# THS3201.net
KiCad netlist of a schematic drawn in Altium Designer
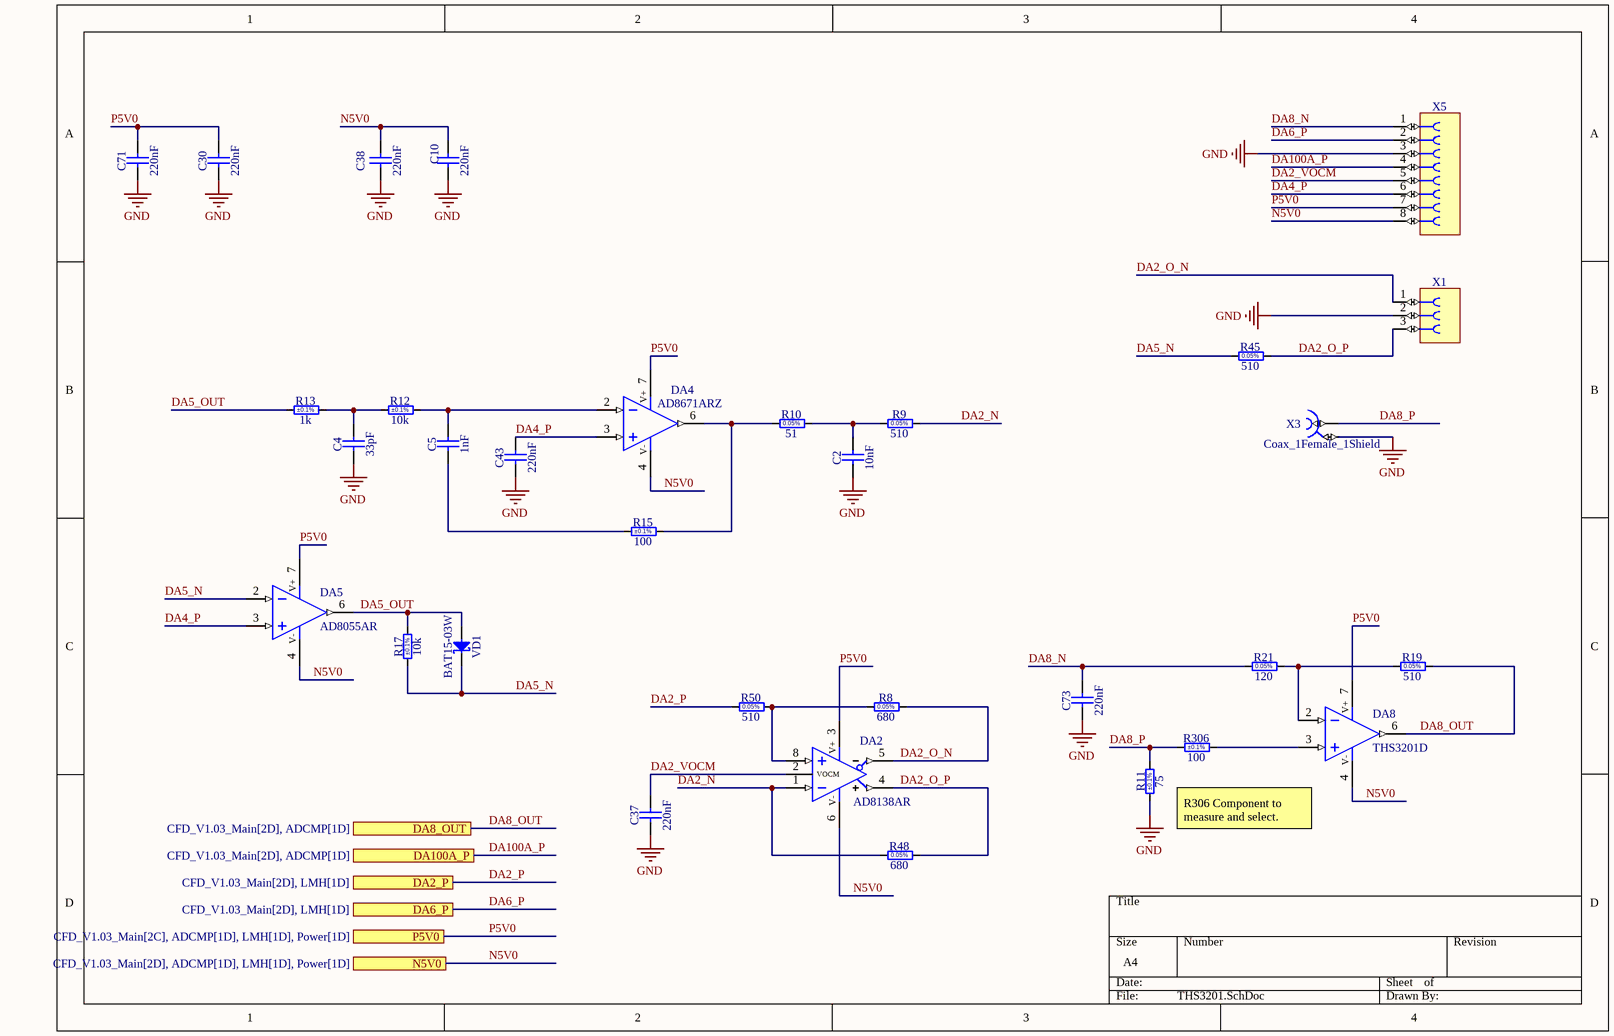
[diagram p0: THS3201.SchDoc]

(export (version "E")
  (design (tool "Eeschema 10.0.6"))
  (components
    (comp (ref "C2")
      (value "10nF")
      (footprint "CAPC2012X135N")
      (description "Non-polarised capacitor")
      (fields
        (field (name "PART NUMBER") "CC0805_10NF_50V_2%_C0G")
        (field (name "VOLTAGE") "50V")
        (field (name "AUTHOR") "CERN DEM HF")
      )
      (libsource (lib "Capacitors") (part "Capacitor - non polarized"))
    )
    (comp (ref "C4")
      (value "33pF")
      (footprint "CAPC2013X115N")
      (description "Non-polarised capacitor")
      (fields
        (field (name "PART NUMBER") "CC0805_33PF_200V_1%_NP0")
        (field (name "VOLTAGE") "200V")
        (field (name "AUTHOR") "CERN DEM HF")
      )
      (libsource (lib "Capacitors") (part "Capacitor - non polarized"))
    )
    (comp (ref "C5")
      (value "1nF")
      (footprint "CAPC2013X100N")
      (description "Non-polarised capacitor")
      (fields
        (field (name "PART NUMBER") "CC0805_1NF_25V_1%_C0G")
        (field (name "VOLTAGE") "25V")
        (field (name "AUTHOR") "CERN DEM JLC")
      )
      (libsource (lib "Capacitors") (part "Capacitor - non polarized"))
    )
    (comp (ref "C10")
      (value "220nF")
      (footprint "CAPC2012X135N")
      (description "Non-polarised capacitor")
      (fields
        (field (name "PART NUMBER") "CC0805_220NF_50V_10%_X7R")
        (field (name "VOLTAGE") "50V")
        (field (name "AUTHOR") "CERN DEM JLC")
      )
      (libsource (lib "Capacitors") (part "Capacitor - non polarized"))
    )
    (comp (ref "C30")
      (value "220nF")
      (footprint "CAPC2012X135N")
      (description "Non-polarised capacitor")
      (fields
        (field (name "PART NUMBER") "CC0805_220NF_50V_10%_X7R")
        (field (name "VOLTAGE") "50V")
        (field (name "AUTHOR") "CERN DEM JLC")
      )
      (libsource (lib "Capacitors") (part "Capacitor - non polarized"))
    )
    (comp (ref "C37")
      (value "220nF")
      (footprint "CAPC2012X135N")
      (description "Non-polarised capacitor")
      (fields
        (field (name "PART NUMBER") "CC0805_220NF_50V_10%_X7R")
        (field (name "VOLTAGE") "50V")
        (field (name "AUTHOR") "CERN DEM JLC")
      )
      (libsource (lib "Capacitors") (part "Capacitor - non polarized"))
    )
    (comp (ref "C38")
      (value "220nF")
      (footprint "CAPC2012X135N")
      (description "Non-polarised capacitor")
      (fields
        (field (name "PART NUMBER") "CC0805_220NF_50V_10%_X7R")
        (field (name "VOLTAGE") "50V")
        (field (name "AUTHOR") "CERN DEM JLC")
      )
      (libsource (lib "Capacitors") (part "Capacitor - non polarized"))
    )
    (comp (ref "C43")
      (value "220nF")
      (footprint "CAPC2012X135N")
      (description "Non-polarised capacitor")
      (fields
        (field (name "PART NUMBER") "CC0805_220NF_50V_10%_X7R")
        (field (name "VOLTAGE") "50V")
        (field (name "AUTHOR") "CERN DEM JLC")
      )
      (libsource (lib "Capacitors") (part "Capacitor - non polarized"))
    )
    (comp (ref "C71")
      (value "220nF")
      (footprint "CAPC2012X135N")
      (description "Non-polarised capacitor")
      (fields
        (field (name "PART NUMBER") "CC0805_220NF_50V_10%_X7R")
        (field (name "VOLTAGE") "50V")
        (field (name "AUTHOR") "CERN DEM JLC")
      )
      (libsource (lib "Capacitors") (part "Capacitor - non polarized"))
    )
    (comp (ref "C73")
      (value "220nF")
      (footprint "CAPC2012X135N")
      (description "Non-polarised capacitor")
      (fields
        (field (name "PART NUMBER") "CC0805_220NF_50V_10%_X7R")
        (field (name "VOLTAGE") "50V")
        (field (name "AUTHOR") "CERN DEM JLC")
      )
      (libsource (lib "Capacitors") (part "Capacitor - non polarized"))
    )
    (comp (ref "DA2")
      (value "AD8138AR")
      (footprint "SOIC127P600X175-8N")
      (description "Differential Amplifier")
      (fields (field (name "MANUFACTURER") "ANALOG DEVICES") (field (name "AUTHOR") "CERN DEM JLC"))
      (libsource (lib "ICs And Semiconductors") (part "Differential Amplifier Type1"))
    )
    (comp (ref "DA4")
      (value "AD8671ARZ")
      (footprint "SOIC127P600X175-8N")
      (description "Operational Amplifier")
      (fields
        (field (name "MANUFACTURER") "ANALOG DEVICES")
        (field (name "MANUFACTURER PART NUMBER") "AD8671AR")
        (field (name "AUTHOR") "CERN DEM JLC")
      )
      (libsource (lib "ICs And Semiconductors") (part "Operational Amplifier Type1"))
    )
    (comp (ref "DA5")
      (value "AD8055AR")
      (footprint "SOIC127P600X175-8N")
      (description "Operational Amplifier")
      (fields (field (name "MANUFACTURER") "ANALOG DEVICES") (field (name "AUTHOR") "CERN DEM HF"))
      (libsource (lib "ICs And Semiconductors") (part "Operational Amplifier Type1"))
    )
    (comp (ref "DA8")
      (value "THS3201D")
      (footprint "SOIC127P600X175-8N")
      (description "Operational Amplifier")
      (fields (field (name "MANUFACTURER") "TEXAS INSTRUMENTS") (field (name "AUTHOR") "CERN DEM HF"))
      (libsource (lib "ICs And Semiconductors") (part "Operational Amplifier Type1"))
    )
    (comp (ref "R8")
      (value "680")
      (footprint "RESC2012X60N")
      (description "Resistor - 0.05%")
      (fields
        (field (name "PART NUMBER") "R0805_680R_0.05%_0.125W_10PPM")
        (field (name "POWER") "0.1W")
        (field (name "AUTHOR") "CERN DEM HF")
      )
      (libsource (lib "Resistors") (part "Resistor - 0.05%"))
    )
    (comp (ref "R9")
      (value "510")
      (footprint "RESC1608X55N")
      (description "Resistor - 0.05%")
      (fields
        (field (name "PART NUMBER") "R0603_510R_0.1%_0.1W_10PPM")
        (field (name "POWER") "0.1W")
        (field (name "AUTHOR") "CERN DEM HF")
      )
      (libsource (lib "Resistors") (part "Resistor - 0.05%"))
    )
    (comp (ref "R10")
      (value "51")
      (footprint "RESC2012X60N")
      (description "Resistor - 0.05%")
      (fields
        (field (name "PART NUMBER") "R0805_51R_0.05%_0.125W_10PPM")
        (field (name "POWER") "0.1W")
        (field (name "AUTHOR") "CERN DEM HF")
      )
      (libsource (lib "Resistors") (part "Resistor - 0.05%"))
    )
    (comp (ref "R11")
      (value "75")
      (footprint "RESC1608X55N")
      (description "Resistor - 0.1%")
      (fields
        (field (name "TOLERANCE") "±0.1%")
        (field (name "PART NUMBER") "R0603_75R_0.1%_0.063W_10PPM")
        (field (name "POWER") "0.063W")
        (field (name "AUTHOR") "CERN DEM JLC")
      )
      (libsource (lib "Resistors") (part "Resistor - 0.1%"))
    )
    (comp (ref "R12")
      (value "10k")
      (footprint "RESC2012X60N")
      (description "Resistor - 0.1%")
      (fields
        (field (name "TOLERANCE") "±0.1%")
        (field (name "PART NUMBER") "R0805_10K_0.1%_0.1W_10PPM")
        (field (name "POWER") "0.1W")
        (field (name "AUTHOR") "CERN DEM JLC")
      )
      (libsource (lib "Resistors") (part "Resistor - 0.1%"))
    )
    (comp (ref "R13")
      (value "1k")
      (footprint "RESC2012X60N")
      (description "Resistor - 0.1%")
      (fields
        (field (name "TOLERANCE") "±0.1%")
        (field (name "PART NUMBER") "R0805_1K_0.1%_0.1W_10PPM")
        (field (name "POWER") "0.1W")
        (field (name "AUTHOR") "CERN DEM JLC")
      )
      (libsource (lib "Resistors") (part "Resistor - 0.1%"))
    )
    (comp (ref "R15")
      (value "100")
      (footprint "RESC2012X60N")
      (description "Resistor - 0.1%")
      (fields
        (field (name "TOLERANCE") "±0.1%")
        (field (name "PART NUMBER") "R0805_100R_0.1%_0.1W_10PPM")
        (field (name "POWER") "0.1W")
        (field (name "AUTHOR") "CERN DEM JLC")
      )
      (libsource (lib "Resistors") (part "Resistor - 0.1%"))
    )
    (comp (ref "R17")
      (value "10k")
      (footprint "RESC2012X60N")
      (description "Resistor - 0.1%")
      (fields
        (field (name "TOLERANCE") "±0.1%")
        (field (name "PART NUMBER") "R0805_10K_0.1%_0.1W_10PPM")
        (field (name "POWER") "0.1W")
        (field (name "AUTHOR") "CERN DEM JLC")
      )
      (libsource (lib "Resistors") (part "Resistor - 0.1%"))
    )
    (comp (ref "R19")
      (value "510")
      (footprint "RESC1608X55N")
      (description "Resistor - 0.05%")
      (fields
        (field (name "PART NUMBER") "R0603_510R_0.1%_0.1W_10PPM")
        (field (name "POWER") "0.1W")
        (field (name "AUTHOR") "CERN DEM HF")
      )
      (libsource (lib "Resistors") (part "Resistor - 0.05%"))
    )
    (comp (ref "R21")
      (value "120")
      (footprint "RESC1608X55N")
      (description "Resistor - 0.05%")
      (fields
        (field (name "PART NUMBER") "R0603_120R_0.05%_0.1W_10PPM")
        (field (name "POWER") "0.1W")
        (field (name "AUTHOR") "CERN DEM HF")
      )
      (libsource (lib "Resistors") (part "Resistor - 0.05%"))
    )
    (comp (ref "R45")
      (value "510")
      (footprint "RESC1608X55N")
      (description "Resistor - 0.05%")
      (fields
        (field (name "PART NUMBER") "R0603_510R_0.1%_0.1W_10PPM")
        (field (name "POWER") "0.1W")
        (field (name "AUTHOR") "CERN DEM HF")
      )
      (libsource (lib "Resistors") (part "Resistor - 0.05%"))
    )
    (comp (ref "R48")
      (value "680")
      (footprint "RESC2012X60N")
      (description "Resistor - 0.05%")
      (fields
        (field (name "PART NUMBER") "R0805_680R_0.05%_0.125W_10PPM")
        (field (name "POWER") "0.1W")
        (field (name "AUTHOR") "CERN DEM HF")
      )
      (libsource (lib "Resistors") (part "Resistor - 0.05%"))
    )
    (comp (ref "R50")
      (value "510")
      (footprint "RESC1608X55N")
      (description "Resistor - 0.05%")
      (fields
        (field (name "PART NUMBER") "R0603_510R_0.1%_0.1W_10PPM")
        (field (name "POWER") "0.1W")
        (field (name "AUTHOR") "CERN DEM HF")
      )
      (libsource (lib "Resistors") (part "Resistor - 0.05%"))
    )
    (comp (ref "R306")
      (value "100")
      (footprint "RESC1005X35N")
      (description "Resistor - 0.1%")
      (fields
        (field (name "TOLERANCE") "±0.1%")
        (field (name "PART NUMBER") "R0402_100R_0.1%_0.063W_25PPM")
        (field (name "POWER") "0.063W")
        (field (name "AUTHOR") "CERN DEM JMW")
      )
      (libsource (lib "Resistors") (part "Resistor - 0.1%"))
    )
    (comp (ref "VD1")
      (value "BAT15-03W")
      (footprint "SOD2512X110N")
      (description "Schottky Diode")
      (fields
        (field (name "VOLTAGE") "4V")
        (field (name "POWER") "100mA")
        (field (name "AUTHOR") "CERN DEM HF")
      )
      (libsource (lib "ICs And Semiconductors") (part "Diode Schottky"))
    )
    (comp (ref "X1")
      (value "Socket 3")
      (footprint "SAMTEC_CES-103-01-T-S")
      (description "Connector 3 Female")
      (fields
        (field (name "PART NUMBER") "SAMTEC_CES-103-01-L-S")
        (field (name "MANUFACTURER") "SAMTEC")
        (field (name "AUTHOR") "CERN DEM HF")
      )
      (libsource (lib "Connectors") (part "Connector 3 Female"))
    )
    (comp (ref "X3")
      (value "Coax_1Female_1Shield")
      (footprint "SAMTEC_MMCX-J-P-H-ST-TH1")
      (fields
        (field (name "PART NUMBER") "SAMTEC_MMCX-J-P-H-ST-TH1")
        (field (name "MANUFACTURER") "SAMTEC")
        (field (name "MANUFACTURER PART NUMBER") "MMCX-J-P-H-ST-TH1")
        (field (name "AUTHOR") "CERN DEM JLC")
      )
      (libsource (lib "Connectors") (part "Coax_1Female_1Shield"))
    )
    (comp (ref "X5")
      (value "Socket 8")
      (footprint "SAMTEC_CES-108-01-T-S")
      (description "Connector 8 Female")
      (fields
        (field (name "PART NUMBER") "SAMTEC_CES-108-01-L-S")
        (field (name "MANUFACTURER") "SAMTEC")
        (field (name "AUTHOR") "CERN DEM HF")
      )
      (libsource (lib "Connectors") (part "Connector 8 Female"))
    )
  )
  (nets
    (net (code "1") (name "/DA2_N") (class "Default")
      (node (ref "DA2") (pin "1") (pinfunction "IN-_1") (pintype "input"))
      (node (ref "R48") (pin "1") (pinfunction "1_1") (pintype "passive"))
      (node (ref "R9") (pin "2") (pinfunction "2_2") (pintype "passive"))
    )
    (net (code "2") (name "/DA2_O_N") (class "Default")
      (node (ref "DA2") (pin "5") (pinfunction "VOUT-_5") (pintype "output"))
      (node (ref "R8") (pin "2") (pinfunction "2_2") (pintype "passive"))
      (node (ref "X1") (pin "1") (pinfunction "1_1") (pintype "bidirectional"))
    )
    (net (code "3") (name "/DA2_O_P") (class "Default")
      (node (ref "DA2") (pin "4") (pinfunction "VOUT+_4") (pintype "output"))
      (node (ref "R45") (pin "2") (pinfunction "2_2") (pintype "passive"))
      (node (ref "R48") (pin "2") (pinfunction "2_2") (pintype "passive"))
      (node (ref "X1") (pin "3") (pinfunction "3_3") (pintype "bidirectional"))
    )
    (net (code "4") (name "/DA2_P") (class "Default")
      (node (ref "R50") (pin "1") (pinfunction "1_1") (pintype "passive"))
    )
    (net (code "5") (name "/DA2_VOCM") (class "Default")
      (node (ref "C37") (pin "2") (pinfunction "2_2") (pintype "passive"))
      (node (ref "DA2") (pin "2") (pinfunction "VOCM_2") (pintype "passive"))
      (node (ref "X5") (pin "5") (pinfunction "5_5") (pintype "bidirectional"))
    )
    (net (code "6") (name "/DA4_P") (class "Default")
      (node (ref "C43") (pin "2") (pinfunction "2_2") (pintype "passive"))
      (node (ref "DA4") (pin "3") (pinfunction "IN+_3") (pintype "input"))
      (node (ref "DA5") (pin "3") (pinfunction "IN+_3") (pintype "input"))
      (node (ref "X5") (pin "6") (pinfunction "6_6") (pintype "bidirectional"))
    )
    (net (code "7") (name "/DA5_N") (class "Default")
      (node (ref "DA5") (pin "2") (pinfunction "IN-_2") (pintype "input"))
      (node (ref "R17") (pin "1") (pinfunction "1_1") (pintype "passive"))
      (node (ref "R45") (pin "1") (pinfunction "1_1") (pintype "passive"))
      (node (ref "VD1") (pin "1") (pinfunction "C_1") (pintype "passive"))
    )
    (net (code "8") (name "/DA5_OUT") (class "Default")
      (node (ref "DA5") (pin "6") (pinfunction "OUT_6") (pintype "output"))
      (node (ref "R13") (pin "1") (pinfunction "1_1") (pintype "passive"))
      (node (ref "R17") (pin "2") (pinfunction "2_2") (pintype "passive"))
      (node (ref "VD1") (pin "2") (pinfunction "A_2") (pintype "passive"))
    )
    (net (code "9") (name "/DA6_P") (class "Default")
      (node (ref "X5") (pin "2") (pinfunction "2_2") (pintype "bidirectional"))
    )
    (net (code "10") (name "/DA8_N") (class "Default")
      (node (ref "C73") (pin "2") (pinfunction "2_2") (pintype "passive"))
      (node (ref "R21") (pin "1") (pinfunction "1_1") (pintype "passive"))
      (node (ref "X5") (pin "1") (pinfunction "1_1") (pintype "bidirectional"))
    )
    (net (code "11") (name "/DA8_OUT") (class "Default")
      (node (ref "DA8") (pin "6") (pinfunction "OUT_6") (pintype "output"))
      (node (ref "R19") (pin "2") (pinfunction "2_2") (pintype "passive"))
    )
    (net (code "12") (name "/DA8_P") (class "Default")
      (node (ref "R11") (pin "2") (pinfunction "2_2") (pintype "passive"))
      (node (ref "R306") (pin "1") (pinfunction "1_1") (pintype "passive"))
      (node (ref "X3") (pin "1") (pinfunction "1_1") (pintype "bidirectional"))
    )
    (net (code "13") (name "/DA100A_P") (class "Default")
      (node (ref "X5") (pin "4") (pinfunction "4_4") (pintype "bidirectional"))
    )
    (net (code "14") (name "/N5V0") (class "Default")
      (node (ref "C10") (pin "2") (pinfunction "2_2") (pintype "passive"))
      (node (ref "C38") (pin "2") (pinfunction "2_2") (pintype "passive"))
      (node (ref "DA2") (pin "6") (pinfunction "V-_6") (pintype "power_in"))
      (node (ref "DA4") (pin "4") (pinfunction "V-_4") (pintype "power_in"))
      (node (ref "DA5") (pin "4") (pinfunction "V-_4") (pintype "power_in"))
      (node (ref "DA8") (pin "4") (pinfunction "V-_4") (pintype "power_in"))
      (node (ref "X5") (pin "8") (pinfunction "8_8") (pintype "bidirectional"))
    )
    (net (code "15") (name "/P5V0") (class "Default")
      (node (ref "C30") (pin "2") (pinfunction "2_2") (pintype "passive"))
      (node (ref "C71") (pin "2") (pinfunction "2_2") (pintype "passive"))
      (node (ref "DA2") (pin "3") (pinfunction "V+_3") (pintype "power_in"))
      (node (ref "DA4") (pin "7") (pinfunction "V+_7") (pintype "power_in"))
      (node (ref "DA5") (pin "7") (pinfunction "V+_7") (pintype "power_in"))
      (node (ref "DA8") (pin "7") (pinfunction "V+_7") (pintype "power_in"))
      (node (ref "X5") (pin "7") (pinfunction "7_7") (pintype "bidirectional"))
    )
    (net (code "16") (name "GND") (class "Default")
      (node (ref "C10") (pin "1") (pinfunction "1_1") (pintype "passive"))
      (node (ref "C2") (pin "1") (pinfunction "1_1") (pintype "passive"))
      (node (ref "C30") (pin "1") (pinfunction "1_1") (pintype "passive"))
      (node (ref "C37") (pin "1") (pinfunction "1_1") (pintype "passive"))
      (node (ref "C38") (pin "1") (pinfunction "1_1") (pintype "passive"))
      (node (ref "C4") (pin "1") (pinfunction "1_1") (pintype "passive"))
      (node (ref "C43") (pin "1") (pinfunction "1_1") (pintype "passive"))
      (node (ref "C71") (pin "1") (pinfunction "1_1") (pintype "passive"))
      (node (ref "C73") (pin "1") (pinfunction "1_1") (pintype "passive"))
      (node (ref "R11") (pin "1") (pinfunction "1_1") (pintype "passive"))
      (node (ref "X1") (pin "2") (pinfunction "2_2") (pintype "bidirectional"))
      (node (ref "X3") (pin "2") (pinfunction "2_2") (pintype "bidirectional"))
      (node (ref "X5") (pin "3") (pinfunction "3_3") (pintype "bidirectional"))
    )
    (net (code "17") (name "Net-(C2-Pad2)") (class "Default")
      (node (ref "C2") (pin "2") (pinfunction "2_2") (pintype "passive"))
      (node (ref "R10") (pin "2") (pinfunction "2_2") (pintype "passive"))
      (node (ref "R9") (pin "1") (pinfunction "1_1") (pintype "passive"))
    )
    (net (code "18") (name "Net-(C4-Pad2)") (class "Default")
      (node (ref "C4") (pin "2") (pinfunction "2_2") (pintype "passive"))
      (node (ref "R12") (pin "1") (pinfunction "1_1") (pintype "passive"))
      (node (ref "R13") (pin "2") (pinfunction "2_2") (pintype "passive"))
    )
    (net (code "19") (name "Net-(C5-Pad1)") (class "Default")
      (node (ref "C5") (pin "1") (pinfunction "1_1") (pintype "passive"))
      (node (ref "R15") (pin "1") (pinfunction "1_1") (pintype "passive"))
    )
    (net (code "20") (name "Net-(DA2-IN+)") (class "Default")
      (node (ref "DA2") (pin "8") (pinfunction "IN+_8") (pintype "input"))
      (node (ref "R50") (pin "2") (pinfunction "2_2") (pintype "passive"))
      (node (ref "R8") (pin "1") (pinfunction "1_1") (pintype "passive"))
    )
    (net (code "21") (name "Net-(DA4-IN-)") (class "Default")
      (node (ref "C5") (pin "2") (pinfunction "2_2") (pintype "passive"))
      (node (ref "DA4") (pin "2") (pinfunction "IN-_2") (pintype "input"))
      (node (ref "R12") (pin "2") (pinfunction "2_2") (pintype "passive"))
    )
    (net (code "22") (name "Net-(DA4-OUT)") (class "Default")
      (node (ref "DA4") (pin "6") (pinfunction "OUT_6") (pintype "output"))
      (node (ref "R10") (pin "1") (pinfunction "1_1") (pintype "passive"))
      (node (ref "R15") (pin "2") (pinfunction "2_2") (pintype "passive"))
    )
    (net (code "23") (name "Net-(DA8-IN+)") (class "Default")
      (node (ref "DA8") (pin "3") (pinfunction "IN+_3") (pintype "input"))
      (node (ref "R306") (pin "2") (pinfunction "2_2") (pintype "passive"))
    )
    (net (code "24") (name "Net-(DA8-IN-)") (class "Default")
      (node (ref "DA8") (pin "2") (pinfunction "IN-_2") (pintype "input"))
      (node (ref "R19") (pin "1") (pinfunction "1_1") (pintype "passive"))
      (node (ref "R21") (pin "2") (pinfunction "2_2") (pintype "passive"))
    )
  )
)
